# 3Dheater3.net
KiCad netlist of a schematic drawn in Altium Designer
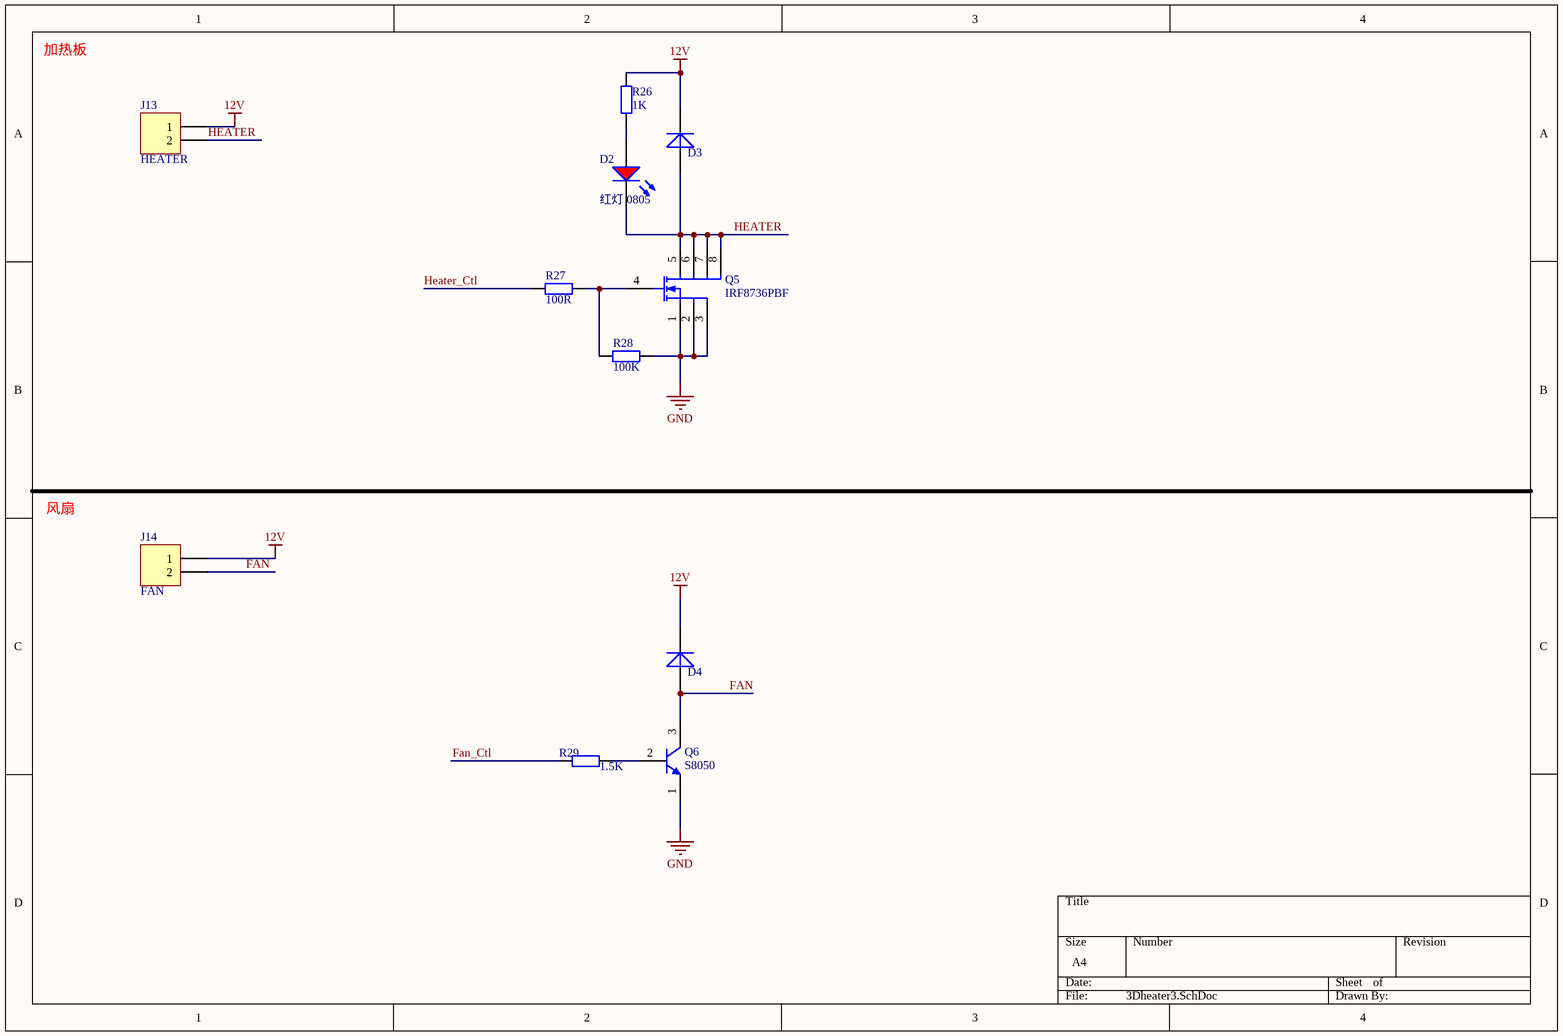
[diagram p0: 3Dheater3.SchDoc]

(export (version "E")
  (design (tool "Eeschema 10.0.6"))
  (components
    (comp (ref "D2")
      (value "红灯 0805")
      (footprint "0805_LED_S1")
      (description "发光二极管")
      (libsource (lib "Miscellaneous Devices LC") (part "0805 红灯"))
    )
    (comp (ref "D3")
      (value "S1G")
      (footprint "DO214AC (SMA)")
      (description "RO DIODE S1G DO-214AC")
      (libsource (lib "Database_Faber") (part "Diode"))
    )
    (comp (ref "D4")
      (value "S1G")
      (footprint "DO214AC (SMA)")
      (description "RO DIODE S1G DO-214AC")
      (libsource (lib "Database_Faber") (part "Diode"))
    )
    (comp (ref "J13")
      (value "HEATER")
      (footprint "HDR1X2")
      (description "Header, 2-Pin, Right Angle")
      (fields (field (name "PUBLISHER") "Altium Limited"))
      (libsource (lib "Miscellaneous Connectors") (part "Header 2H"))
    )
    (comp (ref "J14")
      (value "FAN")
      (footprint "HDR1X2")
      (description "Header, 2-Pin, Right Angle")
      (fields (field (name "PUBLISHER") "Altium Limited"))
      (libsource (lib "Miscellaneous Connectors") (part "Header 2H"))
    )
    (comp (ref "Q5")
      (value "IRF8736PBF")
      (footprint "SOIC127P600X175-8N (SO8)")
      (description "IRF8736PBF - MOSFET, N SO-8")
      (fields (field (name "MFG") "INTERNATIONAL RECTIFIER"))
      (libsource (lib "Database_Faber") (part "MOSFET-N-SO8"))
    )
    (comp (ref "Q6")
      (value "S8050")
      (footprint "Miscellaneous Devices LC:SOT-23-3L")
      (description "NPN三极管")
      (fields (field (name "PUBLISHER") "Altium Limited"))
      (libsource (lib "fszhang") (part "S8050"))
    )
    (comp (ref "R26")
      (value "1K")
      (footprint "R0805")
      (description "贴片电阻")
      (fields (field (name "PUBLISHER") "Altium Limited"))
      (libsource (lib "") (part "Res1_2"))
    )
    (comp (ref "R27")
      (value "100R")
      (footprint "R0805")
      (description "贴片电阻")
      (fields (field (name "PUBLISHER") "Altium Limited"))
      (libsource (lib "fszhang") (part "Res1"))
    )
    (comp (ref "R28")
      (value "100K")
      (footprint "R0805")
      (description "贴片电阻")
      (fields (field (name "PUBLISHER") "Altium Limited"))
      (libsource (lib "fszhang") (part "Res1"))
    )
    (comp (ref "R29")
      (value "1.5K")
      (footprint "R0805")
      (description "贴片电阻")
      (fields (field (name "PUBLISHER") "Altium Limited"))
      (libsource (lib "") (part "Res1_1"))
    )
  )
  (nets
    (net (code "1") (name "/FAN") (class "Default")
      (node (ref "D4") (pin "1") (pinfunction "A_1") (pintype "passive"))
      (node (ref "J14") (pin "2") (pinfunction "2_2") (pintype "passive"))
      (node (ref "Q6") (pin "3") (pinfunction "C_3") (pintype "passive"))
    )
    (net (code "2") (name "/Fan_Ctl") (class "Default")
      (node (ref "R29") (pin "2") (pinfunction "2_2") (pintype "passive"))
    )
    (net (code "3") (name "/HEATER") (class "Default")
      (node (ref "D2") (pin "K") (pinfunction "K_K") (pintype "passive"))
      (node (ref "D3") (pin "1") (pinfunction "A_1") (pintype "passive"))
      (node (ref "J13") (pin "2") (pinfunction "2_2") (pintype "passive"))
      (node (ref "Q5") (pin "5") (pinfunction "D_5") (pintype "passive"))
      (node (ref "Q5") (pin "6") (pinfunction "D_6") (pintype "passive"))
      (node (ref "Q5") (pin "7") (pinfunction "D_7") (pintype "passive"))
      (node (ref "Q5") (pin "8") (pinfunction "D_8") (pintype "passive"))
    )
    (net (code "4") (name "/Heater_Ctl") (class "Default")
      (node (ref "R27") (pin "1") (pinfunction "1_1") (pintype "passive"))
    )
    (net (code "5") (name "12V") (class "Default")
      (node (ref "D3") (pin "2") (pinfunction "K_2") (pintype "passive"))
      (node (ref "D4") (pin "2") (pinfunction "K_2") (pintype "passive"))
      (node (ref "J13") (pin "1") (pinfunction "1_1") (pintype "passive"))
      (node (ref "J14") (pin "1") (pinfunction "1_1") (pintype "passive"))
      (node (ref "R26") (pin "2") (pinfunction "2_2") (pintype "passive"))
    )
    (net (code "6") (name "GND") (class "Default")
      (node (ref "Q5") (pin "1") (pinfunction "S_1") (pintype "passive"))
      (node (ref "Q5") (pin "2") (pinfunction "S_2") (pintype "passive"))
      (node (ref "Q5") (pin "3") (pinfunction "S_3") (pintype "passive"))
      (node (ref "Q6") (pin "1") (pinfunction "E_1") (pintype "passive"))
      (node (ref "R28") (pin "2") (pinfunction "2_2") (pintype "passive"))
    )
    (net (code "7") (name "Net-(D2-PadA)") (class "Default")
      (node (ref "D2") (pin "A") (pinfunction "A_A") (pintype "passive"))
      (node (ref "R26") (pin "1") (pinfunction "1_1") (pintype "passive"))
    )
    (net (code "8") (name "Net-(Q5-G)") (class "Default")
      (node (ref "Q5") (pin "4") (pinfunction "G_4") (pintype "passive"))
      (node (ref "R27") (pin "2") (pinfunction "2_2") (pintype "passive"))
      (node (ref "R28") (pin "1") (pinfunction "1_1") (pintype "passive"))
    )
    (net (code "9") (name "Net-(Q6-B)") (class "Default")
      (node (ref "Q6") (pin "2") (pinfunction "B_2") (pintype "passive"))
      (node (ref "R29") (pin "1") (pinfunction "1_1") (pintype "passive"))
    )
  )
)
